# NanoRS485-MySens-v002.net
KiCad netlist of a schematic drawn in EAGLE
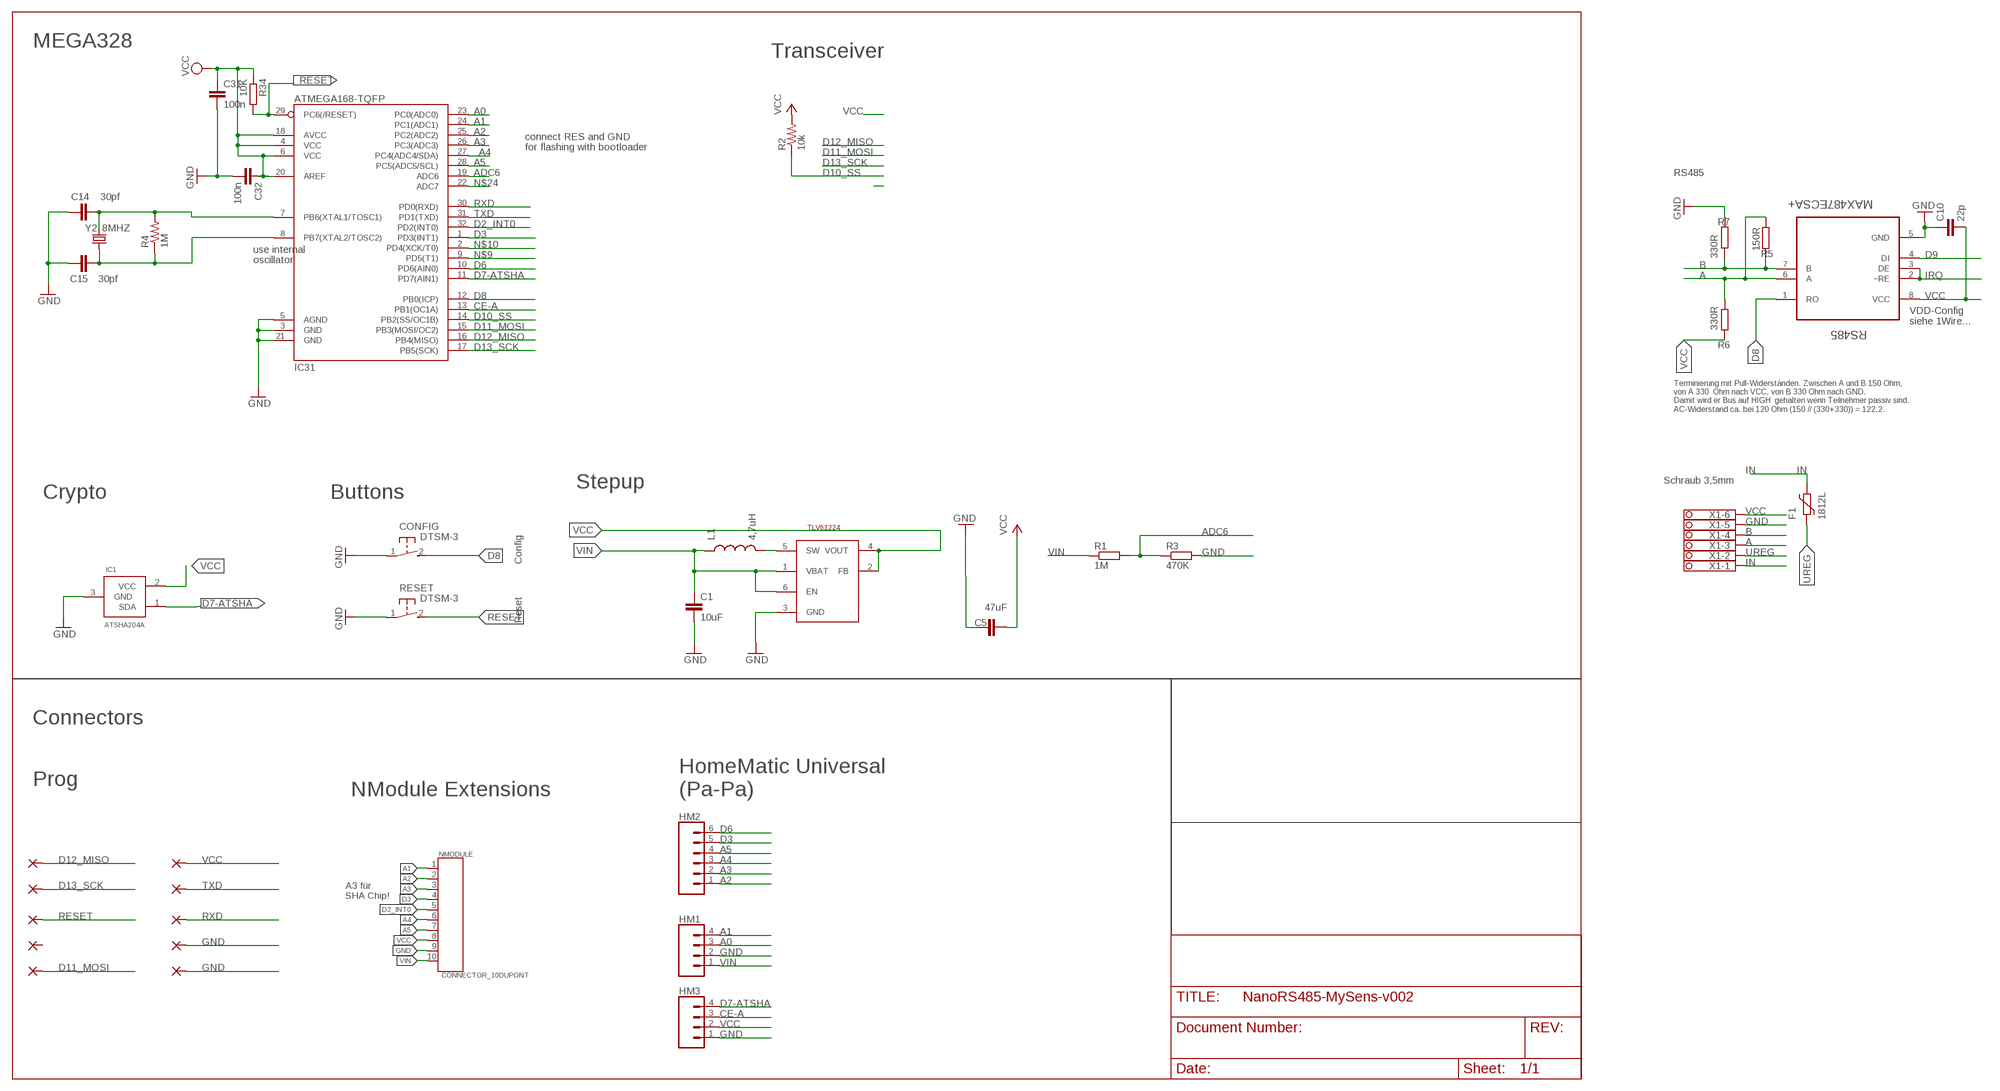
[diagram p0: schematic, sheet 1]

(export (version "E")
  (design (tool "Eeschema 10.0.6"))
  (components
    (comp (ref "C1")
      (value "10uF")
      (footprint "eagle-import:0805")
      (libsource (lib "eagle-import") (part "CAP0805"))
    )
    (comp (ref "C5")
      (value "47uF")
      (footprint "eagle-import:C1210")
      (libsource (lib "eagle-import") (part "C-EUC1210"))
    )
    (comp (ref "C10")
      (value "22p")
      (footprint "eagle-import:C0805")
      (libsource (lib "eagle-import") (part "C-EUC0805"))
    )
    (comp (ref "C14")
      (value "30pf")
      (footprint "eagle-import:0805")
      (libsource (lib "eagle-import") (part "doug_CAP0805"))
    )
    (comp (ref "C15")
      (value "30pf")
      (footprint "eagle-import:0805")
      (libsource (lib "eagle-import") (part "doug_CAP0805"))
    )
    (comp (ref "C31")
      (value "100n")
      (footprint "eagle-import:C0805")
      (libsource (lib "eagle-import") (part "C-EUC0805"))
    )
    (comp (ref "C32")
      (value "100n")
      (footprint "eagle-import:C0805")
      (libsource (lib "eagle-import") (part "C-EUC0805"))
    )
    (comp (ref "CONFIG")
      (value "DTSM-3")
      (footprint "eagle-import:DTSM-3")
      (libsource (lib "eagle-import") (part "DTSM-3"))
    )
    (comp (ref "F1")
      (value "1812L")
      (footprint "eagle-import:1812L")
      (libsource (lib "eagle-import") (part "1812L"))
    )
    (comp (ref "GND")
      (value "WIREPADSMD1,27-254")
      (footprint "eagle-import:SMD1,27-2,54")
      (libsource (lib "eagle-import") (part "WIREPADSMD1,27-254"))
    )
    (comp (ref "GND2")
      (value "WIREPADSMD1,27-254")
      (footprint "eagle-import:SMD1,27-2,54")
      (libsource (lib "eagle-import") (part "WIREPADSMD1,27-254"))
    )
    (comp (ref "HM1")
      (value "CONN_04")
      (footprint "eagle-import:1X04")
      (libsource (lib "eagle-import") (part "CONN_04"))
    )
    (comp (ref "HM2")
      (value "CONN_06SILK_FEMALE_PTH")
      (footprint "eagle-import:1X06")
      (libsource (lib "eagle-import") (part "CONN_06SILK_FEMALE_PTH"))
    )
    (comp (ref "HM3")
      (value "CONN_04")
      (footprint "eagle-import:1X04")
      (libsource (lib "eagle-import") (part "CONN_04"))
    )
    (comp (ref "IC1")
      (value "ATSHA204A")
      (footprint "eagle-import:SOT23")
      (libsource (lib "eagle-import") (part "ATSHA204A"))
    )
    (comp (ref "IC31")
      (value "ATMEGA168-TQFP")
      (footprint "eagle-import:TQFP32-08")
      (libsource (lib "eagle-import") (part "ATMEGA168-TQFP"))
    )
    (comp (ref "L1")
      (value "4,7uH")
      (footprint "eagle-import:0805")
      (libsource (lib "eagle-import") (part "INDUCTOR0805"))
    )
    (comp (ref "MISO")
      (value "WIREPADSMD1,27-254")
      (footprint "eagle-import:SMD1,27-2,54")
      (libsource (lib "eagle-import") (part "WIREPADSMD1,27-254"))
    )
    (comp (ref "MOSI")
      (value "WIREPADSMD1,27-254")
      (footprint "eagle-import:SMD1,27-2,54")
      (libsource (lib "eagle-import") (part "WIREPADSMD1,27-254"))
    )
    (comp (ref "NC")
      (value "WIREPADSMD1,27-254")
      (footprint "eagle-import:SMD1,27-2,54")
      (libsource (lib "eagle-import") (part "WIREPADSMD1,27-254"))
    )
    (comp (ref "NMODULE")
      (value "CONNECTOR_10DUPONT")
      (footprint "eagle-import:DUPONT_10")
      (libsource (lib "eagle-import") (part "CONNECTOR_10DUPONT"))
    )
    (comp (ref "R1")
      (value "1M")
      (footprint "eagle-import:R0805")
      (libsource (lib "eagle-import") (part "R-EU_R0805"))
    )
    (comp (ref "R2")
      (value "10k")
      (footprint "eagle-import:0805")
      (libsource (lib "eagle-import") (part "RESISTOR0805-RES"))
    )
    (comp (ref "R3")
      (value "470K")
      (footprint "eagle-import:R0805")
      (libsource (lib "eagle-import") (part "R-EU_R0805"))
    )
    (comp (ref "R4")
      (value "1M")
      (footprint "eagle-import:0805")
      (libsource (lib "eagle-import") (part "RESISTOR0805-RES"))
    )
    (comp (ref "R5")
      (value "150R")
      (footprint "eagle-import:R0805")
      (libsource (lib "eagle-import") (part "R-EU_R0805"))
    )
    (comp (ref "R6")
      (value "330R")
      (footprint "eagle-import:R0805")
      (libsource (lib "eagle-import") (part "R-EU_R0805"))
    )
    (comp (ref "R7")
      (value "330R")
      (footprint "eagle-import:R0805")
      (libsource (lib "eagle-import") (part "R-EU_R0805"))
    )
    (comp (ref "R34")
      (value "10K")
      (footprint "eagle-import:R0805")
      (libsource (lib "eagle-import") (part "R-EU_R0805"))
    )
    (comp (ref "RESET")
      (value "DTSM-3")
      (footprint "eagle-import:DTSM-3")
      (libsource (lib "eagle-import") (part "DTSM-3"))
    )
    (comp (ref "RS485")
      (value "MAX487ECSA+")
      (footprint "eagle-import:SOIC127P600X175-8N")
      (libsource (lib "eagle-import") (part "MAX487ECSA+"))
    )
    (comp (ref "RST")
      (value "WIREPADSMD1,27-254")
      (footprint "eagle-import:SMD1,27-2,54")
      (libsource (lib "eagle-import") (part "WIREPADSMD1,27-254"))
    )
    (comp (ref "RXD")
      (value "WIREPADSMD1,27-254")
      (footprint "eagle-import:SMD1,27-2,54")
      (libsource (lib "eagle-import") (part "WIREPADSMD1,27-254"))
    )
    (comp (ref "SCK")
      (value "WIREPADSMD1,27-254")
      (footprint "eagle-import:SMD1,27-2,54")
      (libsource (lib "eagle-import") (part "WIREPADSMD1,27-254"))
    )
    (comp (ref "STEPUP")
      (value "TLV61224")
      (footprint "eagle-import:SOT23-6L")
      (libsource (lib "eagle-import") (part "TI-TLV61224"))
    )
    (comp (ref "TXD")
      (value "WIREPADSMD1,27-254")
      (footprint "eagle-import:SMD1,27-2,54")
      (libsource (lib "eagle-import") (part "WIREPADSMD1,27-254"))
    )
    (comp (ref "VCC")
      (value "WIREPADSMD1,27-254")
      (footprint "eagle-import:SMD1,27-2,54")
      (libsource (lib "eagle-import") (part "WIREPADSMD1,27-254"))
    )
    (comp (ref "X1")
      (value "1751280")
      (footprint "eagle-import:1751280")
      (libsource (lib "eagle-import") (part "1751280"))
    )
    (comp (ref "Y2")
      (value "8MHZ")
      (footprint "eagle-import:CRYSTAL-TXC-7A")
      (libsource (lib "eagle-import") (part "CRYSTALTXC-7A"))
    )
  )
  (nets
    (net (code "1") (name "/A") (class "Default")
      (node (ref "R5") (pin "1") (pinfunction "1_1") (pintype "passive"))
      (node (ref "R6") (pin "2") (pinfunction "2_2") (pintype "passive"))
      (node (ref "RS485") (pin "6") (pinfunction "A_6") (pintype "bidirectional"))
      (node (ref "X1") (pin "3") (pinfunction "K_3") (pintype "passive"))
    )
    (net (code "2") (name "/A0") (class "Default")
      (node (ref "HM1") (pin "3") (pinfunction "3_3") (pintype "passive"))
      (node (ref "IC31") (pin "23") (pinfunction "PC0(ADC0)_23") (pintype "bidirectional"))
    )
    (net (code "3") (name "/ADC6") (class "Default")
      (node (ref "IC31") (pin "19") (pinfunction "ADC6_19") (pintype "bidirectional"))
      (node (ref "R1") (pin "2") (pinfunction "2_2") (pintype "passive"))
      (node (ref "R3") (pin "1") (pinfunction "1_1") (pintype "passive"))
    )
    (net (code "4") (name "/B") (class "Default")
      (node (ref "R5") (pin "2") (pinfunction "2_2") (pintype "passive"))
      (node (ref "R7") (pin "1") (pinfunction "1_1") (pintype "passive"))
      (node (ref "RS485") (pin "7") (pinfunction "B_7") (pintype "bidirectional"))
      (node (ref "X1") (pin "4") (pinfunction "K_4") (pintype "passive"))
    )
    (net (code "5") (name "/CE-A") (class "Default")
      (node (ref "HM3") (pin "3") (pinfunction "3_3") (pintype "passive"))
      (node (ref "IC31") (pin "13") (pinfunction "PB1(OC1A)_13") (pintype "bidirectional"))
    )
    (net (code "6") (name "/D6") (class "Default")
      (node (ref "HM2") (pin "6") (pinfunction "6_6") (pintype "passive"))
      (node (ref "IC31") (pin "10") (pinfunction "PD6(AIN0)_10") (pintype "bidirectional"))
    )
    (net (code "7") (name "/D7-ATSHA") (class "Default")
      (node (ref "HM3") (pin "4") (pinfunction "4_4") (pintype "passive"))
      (node (ref "IC1") (pin "1") (pinfunction "SDA_1") (pintype "bidirectional"))
      (node (ref "IC31") (pin "11") (pinfunction "PD7(AIN1)_11") (pintype "bidirectional"))
    )
    (net (code "8") (name "/D9") (class "Default")
      (node (ref "RS485") (pin "4") (pinfunction "DI_4") (pintype "input"))
    )
    (net (code "9") (name "/D10_SS") (class "Default")
      (node (ref "IC31") (pin "14") (pinfunction "PB2(SS/OC1B)_14") (pintype "bidirectional"))
      (node (ref "R2") (pin "1") (pinfunction "1_1") (pintype "passive"))
    )
    (net (code "10") (name "/D11_MOSI") (class "Default")
      (node (ref "IC31") (pin "15") (pinfunction "PB3(MOSI/OC2)_15") (pintype "bidirectional"))
      (node (ref "MOSI") (pin "1") (pinfunction "P_1") (pintype "passive"))
    )
    (net (code "11") (name "/D12_MISO") (class "Default")
      (node (ref "IC31") (pin "16") (pinfunction "PB4(MISO)_16") (pintype "bidirectional"))
      (node (ref "MISO") (pin "1") (pinfunction "P_1") (pintype "passive"))
    )
    (net (code "12") (name "/D13_SCK") (class "Default")
      (node (ref "IC31") (pin "17") (pinfunction "PB5(SCK)_17") (pintype "bidirectional"))
      (node (ref "SCK") (pin "1") (pinfunction "P_1") (pintype "passive"))
    )
    (net (code "13") (name "/IN") (class "Default")
      (node (ref "F1") (pin "P$2") (pinfunction "2_P$2") (pintype "passive"))
      (node (ref "X1") (pin "1") (pinfunction "K_1") (pintype "passive"))
    )
    (net (code "14") (name "/IRQ") (class "Default")
      (node (ref "RS485") (pin "2") (pinfunction "~{RE}_2") (pintype "input"))
      (node (ref "RS485") (pin "3") (pinfunction "DE_3") (pintype "input"))
    )
    (net (code "15") (name "/N$9") (class "Default")
      (node (ref "IC31") (pin "9") (pinfunction "PD5(T1)_9") (pintype "bidirectional"))
    )
    (net (code "16") (name "/N$10") (class "Default")
      (node (ref "IC31") (pin "2") (pinfunction "PD4(XCK/T0)_2") (pintype "bidirectional"))
    )
    (net (code "17") (name "/N$24") (class "Default")
      (node (ref "IC31") (pin "22") (pinfunction "ADC7_22") (pintype "bidirectional"))
    )
    (net (code "18") (name "/RXD") (class "Default")
      (node (ref "IC31") (pin "30") (pinfunction "PD0(RXD)_30") (pintype "bidirectional"))
      (node (ref "RXD") (pin "1") (pinfunction "P_1") (pintype "passive"))
    )
    (net (code "19") (name "/TXD") (class "Default")
      (node (ref "IC31") (pin "31") (pinfunction "PD1(TXD)_31") (pintype "bidirectional"))
      (node (ref "TXD") (pin "1") (pinfunction "P_1") (pintype "passive"))
    )
    (net (code "20") (name "A1") (class "Default")
      (node (ref "HM1") (pin "4") (pinfunction "4_4") (pintype "passive"))
      (node (ref "IC31") (pin "24") (pinfunction "PC1(ADC1)_24") (pintype "bidirectional"))
      (node (ref "NMODULE") (pin "1") (pinfunction "1_1") (pintype "bidirectional"))
    )
    (net (code "21") (name "A2") (class "Default")
      (node (ref "HM2") (pin "1") (pinfunction "1_1") (pintype "passive"))
      (node (ref "IC31") (pin "25") (pinfunction "PC2(ADC2)_25") (pintype "bidirectional"))
      (node (ref "NMODULE") (pin "2") (pinfunction "2_2") (pintype "bidirectional"))
    )
    (net (code "22") (name "A3") (class "Default")
      (node (ref "HM2") (pin "2") (pinfunction "2_2") (pintype "passive"))
      (node (ref "IC31") (pin "26") (pinfunction "PC3(ADC3)_26") (pintype "bidirectional"))
      (node (ref "NMODULE") (pin "3") (pinfunction "3_3") (pintype "bidirectional"))
    )
    (net (code "23") (name "A4") (class "Default")
      (node (ref "HM2") (pin "3") (pinfunction "3_3") (pintype "passive"))
      (node (ref "IC31") (pin "27") (pinfunction "PC4(ADC4/SDA)_27") (pintype "bidirectional"))
      (node (ref "NMODULE") (pin "6") (pinfunction "6_6") (pintype "bidirectional"))
    )
    (net (code "24") (name "A5") (class "Default")
      (node (ref "HM2") (pin "4") (pinfunction "4_4") (pintype "passive"))
      (node (ref "IC31") (pin "28") (pinfunction "PC5(ADC5/SCL)_28") (pintype "bidirectional"))
      (node (ref "NMODULE") (pin "7") (pinfunction "7_7") (pintype "bidirectional"))
    )
    (net (code "25") (name "D2_INT0") (class "Default")
      (node (ref "IC31") (pin "32") (pinfunction "PD2(INT0)_32") (pintype "bidirectional"))
      (node (ref "NMODULE") (pin "5") (pinfunction "5_5") (pintype "bidirectional"))
    )
    (net (code "26") (name "D3") (class "Default")
      (node (ref "HM2") (pin "5") (pinfunction "5_5") (pintype "passive"))
      (node (ref "IC31") (pin "1") (pinfunction "PD3(INT1)_1") (pintype "bidirectional"))
      (node (ref "NMODULE") (pin "4") (pinfunction "4_4") (pintype "bidirectional"))
    )
    (net (code "27") (name "D8") (class "Default")
      (node (ref "CONFIG") (pin "2") (pinfunction "2_2") (pintype "passive"))
      (node (ref "IC31") (pin "12") (pinfunction "PB0(ICP)_12") (pintype "bidirectional"))
      (node (ref "RS485") (pin "1") (pinfunction "RO_1") (pintype "output"))
    )
    (net (code "28") (name "GND") (class "Default")
      (node (ref "C1") (pin "2") (pinfunction "2_2") (pintype "passive"))
      (node (ref "C10") (pin "1") (pinfunction "1_1") (pintype "passive"))
      (node (ref "C14") (pin "1") (pinfunction "1_1") (pintype "passive"))
      (node (ref "C15") (pin "1") (pinfunction "1_1") (pintype "passive"))
      (node (ref "C31") (pin "2") (pinfunction "2_2") (pintype "passive"))
      (node (ref "C32") (pin "2") (pinfunction "2_2") (pintype "passive"))
      (node (ref "C5") (pin "1") (pinfunction "1_1") (pintype "passive"))
      (node (ref "CONFIG") (pin "1") (pinfunction "1_1") (pintype "passive"))
      (node (ref "GND") (pin "1") (pinfunction "P_1") (pintype "passive"))
      (node (ref "GND2") (pin "1") (pinfunction "P_1") (pintype "passive"))
      (node (ref "HM1") (pin "2") (pinfunction "2_2") (pintype "passive"))
      (node (ref "HM3") (pin "1") (pinfunction "1_1") (pintype "passive"))
      (node (ref "IC1") (pin "3") (pinfunction "GND_3") (pintype "bidirectional"))
      (node (ref "IC31") (pin "21") (pinfunction "GND_21") (pintype "bidirectional"))
      (node (ref "IC31") (pin "3") (pinfunction "GND_3") (pintype "bidirectional"))
      (node (ref "IC31") (pin "5") (pinfunction "AGND_5") (pintype "bidirectional"))
      (node (ref "NMODULE") (pin "9") (pinfunction "9_9") (pintype "bidirectional"))
      (node (ref "R3") (pin "2") (pinfunction "2_2") (pintype "passive"))
      (node (ref "R7") (pin "2") (pinfunction "2_2") (pintype "passive"))
      (node (ref "RESET") (pin "1") (pinfunction "1_1") (pintype "passive"))
      (node (ref "RS485") (pin "5") (pinfunction "GND_5") (pintype "passive"))
      (node (ref "STEPUP") (pin "3") (pinfunction "GND_3") (pintype "power_in"))
      (node (ref "X1") (pin "5") (pinfunction "K_5") (pintype "passive"))
    )
    (net (code "29") (name "Net-(IC31-PB6(XTAL1{slash}TOSC1))") (class "Default")
      (node (ref "C14") (pin "2") (pinfunction "2_2") (pintype "passive"))
      (node (ref "IC31") (pin "7") (pinfunction "PB6(XTAL1/TOSC1)_7") (pintype "bidirectional"))
      (node (ref "R4") (pin "2") (pinfunction "2_2") (pintype "passive"))
      (node (ref "Y2") (pin "P$2") (pinfunction "2_P$2") (pintype "passive"))
    )
    (net (code "30") (name "Net-(IC31-PB7(XTAL2{slash}TOSC2))") (class "Default")
      (node (ref "C15") (pin "2") (pinfunction "2_2") (pintype "passive"))
      (node (ref "IC31") (pin "8") (pinfunction "PB7(XTAL2/TOSC2)_8") (pintype "bidirectional"))
      (node (ref "R4") (pin "1") (pinfunction "1_1") (pintype "passive"))
      (node (ref "Y2") (pin "P$1") (pinfunction "1_P$1") (pintype "passive"))
    )
    (net (code "31") (name "Net-(STEPUP-SW)") (class "Default")
      (node (ref "L1") (pin "2") (pinfunction "2_2") (pintype "passive"))
      (node (ref "STEPUP") (pin "5") (pinfunction "SW_5") (pintype "power_in"))
    )
    (net (code "32") (name "RESET") (class "Default")
      (node (ref "IC31") (pin "29") (pinfunction "PC6(/RESET)_29") (pintype "bidirectional"))
      (node (ref "R34") (pin "2") (pinfunction "2_2") (pintype "passive"))
      (node (ref "RESET") (pin "2") (pinfunction "2_2") (pintype "passive"))
      (node (ref "RST") (pin "1") (pinfunction "P_1") (pintype "passive"))
    )
    (net (code "33") (name "UREG") (class "Default")
      (node (ref "F1") (pin "P$1") (pinfunction "1_P$1") (pintype "passive"))
      (node (ref "X1") (pin "2") (pinfunction "K_2") (pintype "passive"))
    )
    (net (code "34") (name "VCC") (class "Default")
      (node (ref "C10") (pin "2") (pinfunction "2_2") (pintype "passive"))
      (node (ref "C31") (pin "1") (pinfunction "1_1") (pintype "passive"))
      (node (ref "C32") (pin "1") (pinfunction "1_1") (pintype "passive"))
      (node (ref "C5") (pin "2") (pinfunction "2_2") (pintype "passive"))
      (node (ref "HM3") (pin "2") (pinfunction "2_2") (pintype "passive"))
      (node (ref "IC1") (pin "2") (pinfunction "VCC_2") (pintype "bidirectional"))
      (node (ref "IC31") (pin "18") (pinfunction "AVCC_18") (pintype "bidirectional"))
      (node (ref "IC31") (pin "20") (pinfunction "AREF_20") (pintype "bidirectional"))
      (node (ref "IC31") (pin "4") (pinfunction "VCC_4") (pintype "bidirectional"))
      (node (ref "IC31") (pin "6") (pinfunction "VCC_6") (pintype "bidirectional"))
      (node (ref "NMODULE") (pin "8") (pinfunction "8_8") (pintype "bidirectional"))
      (node (ref "R2") (pin "2") (pinfunction "2_2") (pintype "passive"))
      (node (ref "R34") (pin "1") (pinfunction "1_1") (pintype "passive"))
      (node (ref "R6") (pin "1") (pinfunction "1_1") (pintype "passive"))
      (node (ref "RS485") (pin "8") (pinfunction "VCC_8") (pintype "power_in"))
      (node (ref "STEPUP") (pin "2") (pinfunction "FB_2") (pintype "input"))
      (node (ref "STEPUP") (pin "4") (pinfunction "VOUT_4") (pintype "power_in"))
      (node (ref "VCC") (pin "1") (pinfunction "P_1") (pintype "passive"))
      (node (ref "X1") (pin "6") (pinfunction "K_6") (pintype "passive"))
    )
    (net (code "35") (name "VIN") (class "Default")
      (node (ref "C1") (pin "1") (pinfunction "1_1") (pintype "passive"))
      (node (ref "HM1") (pin "1") (pinfunction "1_1") (pintype "passive"))
      (node (ref "L1") (pin "1") (pinfunction "1_1") (pintype "passive"))
      (node (ref "NMODULE") (pin "10") (pinfunction "10_10") (pintype "bidirectional"))
      (node (ref "R1") (pin "1") (pinfunction "1_1") (pintype "passive"))
      (node (ref "STEPUP") (pin "1") (pinfunction "VBAT_1") (pintype "power_in"))
      (node (ref "STEPUP") (pin "6") (pinfunction "EN_6") (pintype "input"))
    )
    (net (code "36") (name "unconnected-(NC-P-Pad1)") (class "Default")
      (node (ref "NC") (pin "1") (pinfunction "P_1") (pintype "passive"))
    )
  )
)
